# EGS002.net
KiCad netlist of a schematic drawn in Altium Designer
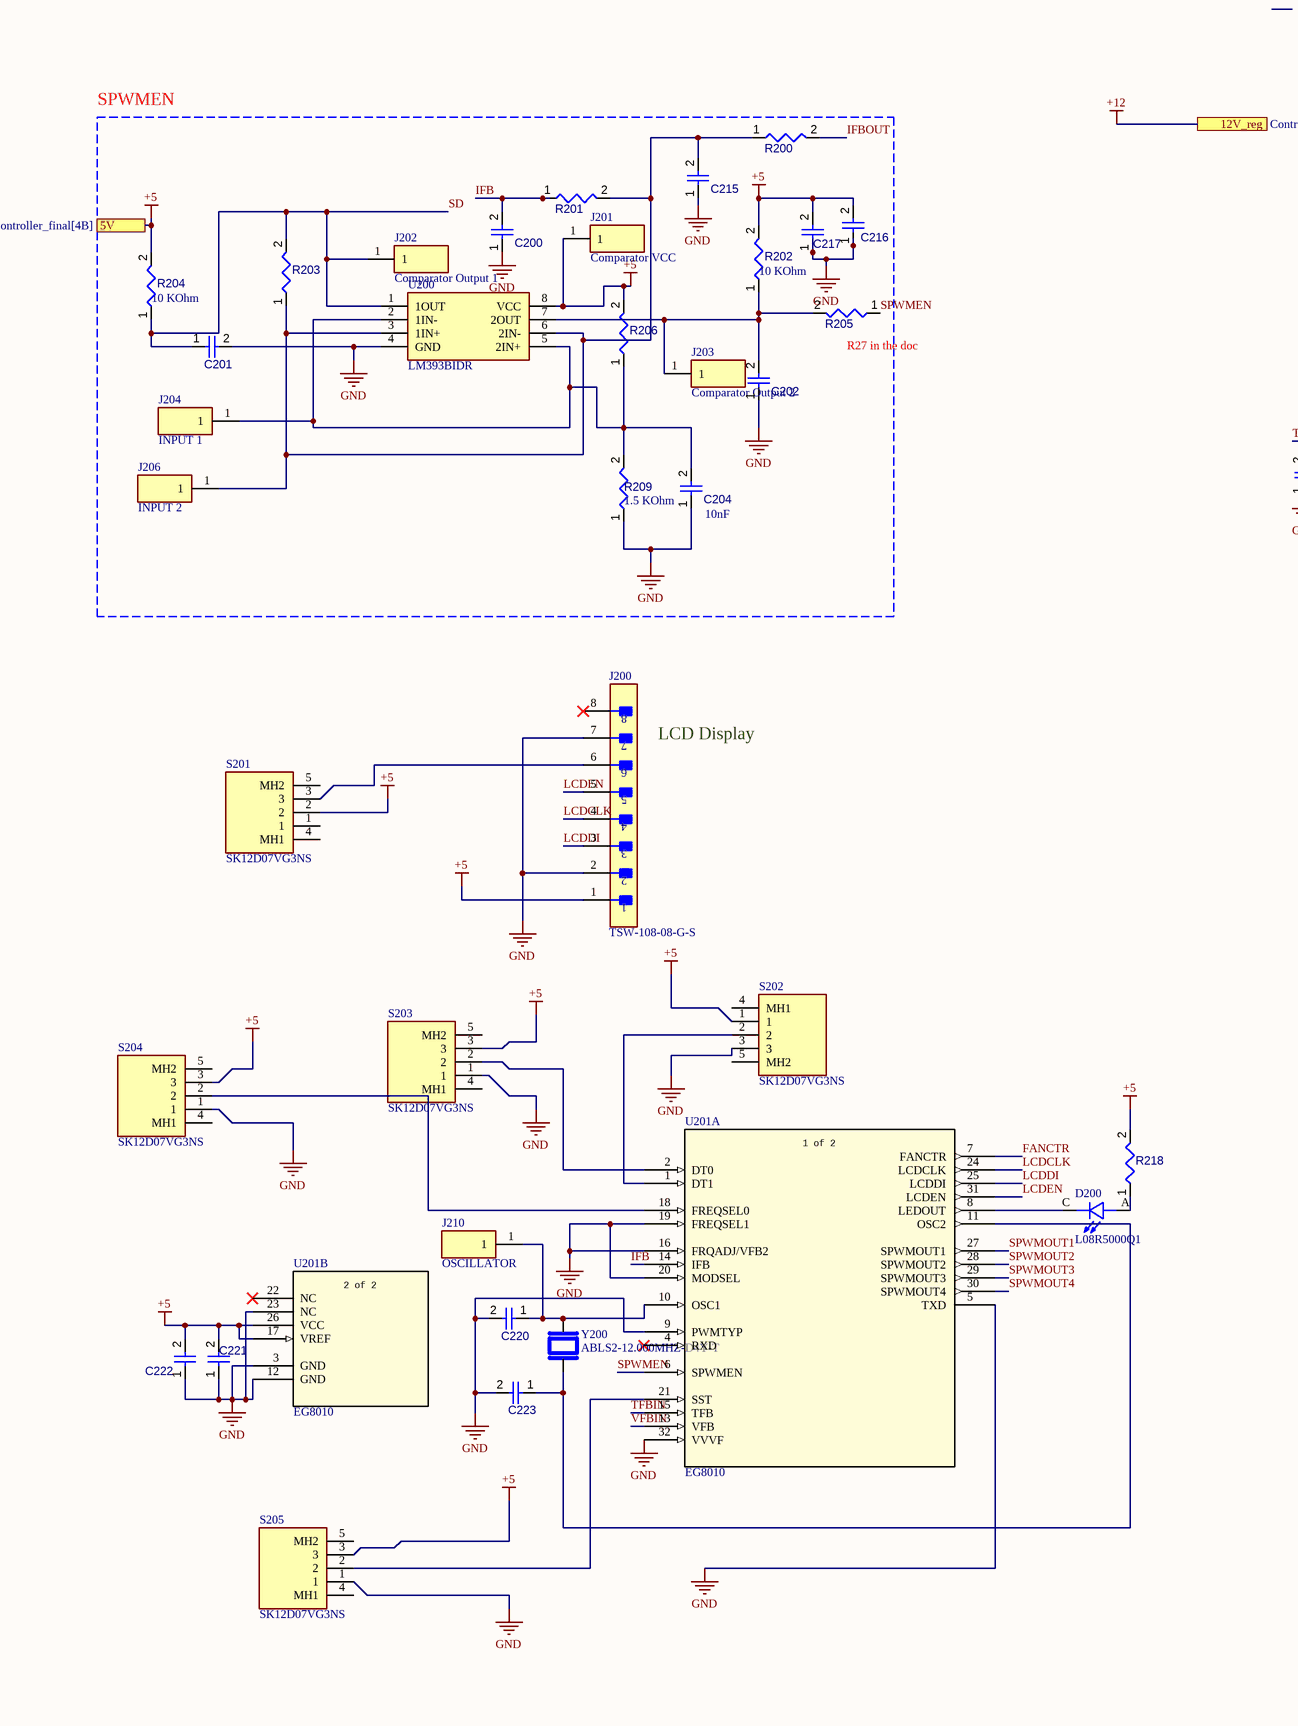
[diagram p0: EGS002.SchDoc, left]
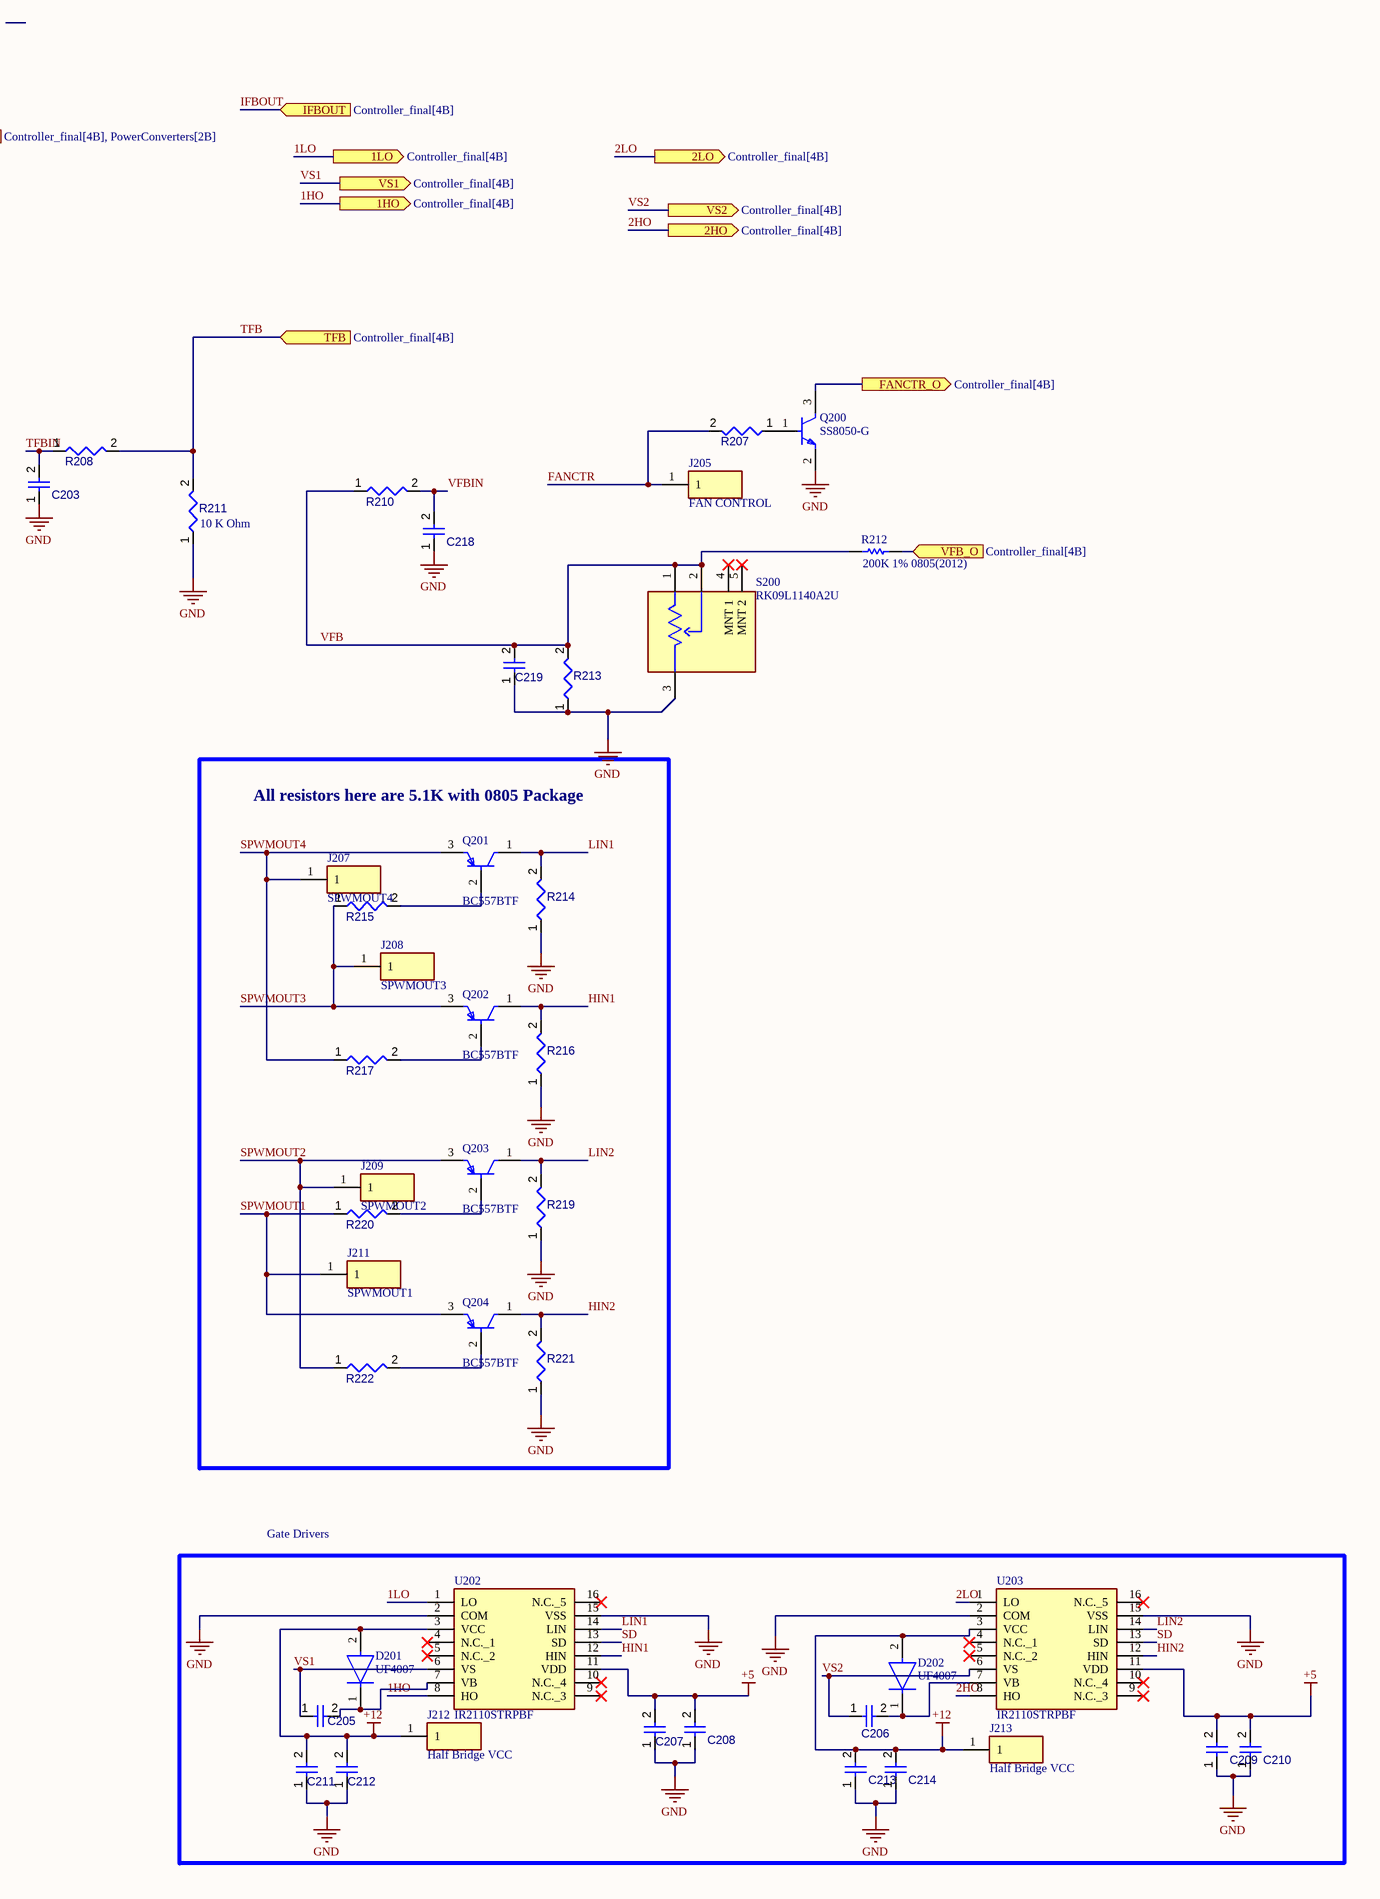
[diagram p1: EGS002.SchDoc, right]

(export (version "E")
  (design (tool "Eeschema 10.0.6"))
  (components
    (comp (ref "C200")
      (value "Capacitor 10nF +/-20% 50V 0402")
      (footprint "CAPC0402(1005)60_L")
      (description "Chip Capacitor, 10nF +/-20%, 50V, 0402, Thickness 0.6 mm")
      (fields (field (name "TOLERANCE") "5%"))
      (libsource (lib "Rahulb 23") (part "CAP-NP-2"))
    )
    (comp (ref "C201")
      (value "Capacitor 1nF +/-20% 50V 0402")
      (footprint "CAPC0402(1005)33_L")
      (description "Chip Capacitor, 1nF +/-20%, 50V, 0402, Thickness 0.33 mm")
      (fields (field (name "TOLERANCE") "10%"))
      (libsource (lib "Rahulb 23") (part "CAP-NP-2"))
    )
    (comp (ref "C202")
      (value "Capacitor 1nF +/-20% 50V 0402")
      (footprint "CAPC0402(1005)33_L")
      (description "Chip Capacitor, 1nF +/-20%, 50V, 0402, Thickness 0.33 mm")
      (fields (field (name "TOLERANCE") "10%"))
      (libsource (lib "Rahulb 23") (part "CAP-NP-2"))
    )
    (comp (ref "C203")
      (value "Capacitor 100 nF +/-10% 50 V 0805")
      (footprint "CAPC2013X95X50LL10T25")
      (description "Chip Capacitor, 100 nF, +/- 10%, 50 V, 0805 (2012 Metric)")
      (fields (field (name "TOLERANCE") "10%"))
      (libsource (lib "Rahulb 23") (part "CAP-NP-2"))
    )
    (comp (ref "C204")
      (value "Capacitor 10nF +/-20% 50V 0402")
      (footprint "CAPC0402(1005)60_L")
      (description "Chip Capacitor, 10nF +/-20%, 50V, 0402, Thickness 0.6 mm")
      (fields (field (name "TOLERANCE") "5%"))
      (libsource (lib "Rahulb 23") (part "CAP-NP-2"))
    )
    (comp (ref "C205")
      (value "Capacitor 10 uF +/- 10% 16 V 0805")
      (footprint "CAPC2013X135X45NL10T25")
      (description "Chip Capacitor, 10 uF, +/- 10%, 16 V, 0805 (2012 Metric)")
      (fields (field (name "TOLERANCE") "10%"))
      (libsource (lib "Rahulb 23") (part "CAP-NP-2"))
    )
    (comp (ref "C206")
      (value "Capacitor 10 uF +/- 10% 16 V 1206")
      (footprint "CAPC3216X180X50NL20T25")
      (description "Chip Capacitor, 10 uF, +/- 10%, 16 V, 1206 (3216 Metric)")
      (fields (field (name "TOLERANCE") "10%"))
      (libsource (lib "Rahulb 23") (part "CAP-NP-2"))
    )
    (comp (ref "C207")
      (value "Capacitor 100 nF +/-10% 50 V 0805")
      (footprint "CAPC2013X95X50LL10T25")
      (description "Chip Capacitor, 100 nF, +/- 10%, 50 V, 0805 (2012 Metric)")
      (fields (field (name "TOLERANCE") "10%"))
      (libsource (lib "Rahulb 23") (part "CAP-NP-2"))
    )
    (comp (ref "C208")
      (value "Capacitor 10 uF +/- 10% 16 V 1206")
      (footprint "CAPC3216X180X50NL20T25")
      (description "Chip Capacitor, 10 uF, +/- 10%, 16 V, 1206 (3216 Metric)")
      (fields (field (name "TOLERANCE") "10%"))
      (libsource (lib "Rahulb 23") (part "CAP-NP-2"))
    )
    (comp (ref "C209")
      (value "Capacitor 100 nF +/-10% 50 V 0805")
      (footprint "CAPC2013X95X50LL10T25")
      (description "Chip Capacitor, 100 nF, +/- 10%, 50 V, 0805 (2012 Metric)")
      (fields (field (name "TOLERANCE") "10%"))
      (libsource (lib "Rahulb 23") (part "CAP-NP-2"))
    )
    (comp (ref "C210")
      (value "Capacitor 10 uF +/- 10% 16 V 1206")
      (footprint "CAPC3216X180X50NL20T25")
      (description "Chip Capacitor, 10 uF, +/- 10%, 16 V, 1206 (3216 Metric)")
      (fields (field (name "TOLERANCE") "10%"))
      (libsource (lib "Rahulb 23") (part "CAP-NP-2"))
    )
    (comp (ref "C211")
      (value "Capacitor 100 nF +/-10% 50 V 0805")
      (footprint "CAPC2013X95X50LL10T25")
      (description "Chip Capacitor, 100 nF, +/- 10%, 50 V, 0805 (2012 Metric)")
      (fields (field (name "TOLERANCE") "10%"))
      (libsource (lib "Rahulb 23") (part "CAP-NP-2"))
    )
    (comp (ref "C212")
      (value "Capacitor 10 uF +/- 10% 16 V 1206")
      (footprint "CAPC3216X180X50NL20T25")
      (description "Chip Capacitor, 10 uF, +/- 10%, 16 V, 1206 (3216 Metric)")
      (fields (field (name "TOLERANCE") "10%"))
      (libsource (lib "Rahulb 23") (part "CAP-NP-2"))
    )
    (comp (ref "C213")
      (value "Capacitor 100 nF +/-10% 50 V 0805")
      (footprint "CAPC2013X95X50LL10T25")
      (description "Chip Capacitor, 100 nF, +/- 10%, 50 V, 0805 (2012 Metric)")
      (fields (field (name "TOLERANCE") "10%"))
      (libsource (lib "Rahulb 23") (part "CAP-NP-2"))
    )
    (comp (ref "C214")
      (value "Capacitor 10 uF +/- 10% 16 V 1206")
      (footprint "CAPC3216X180X50NL20T25")
      (description "Chip Capacitor, 10 uF, +/- 10%, 16 V, 1206 (3216 Metric)")
      (fields (field (name "TOLERANCE") "10%"))
      (libsource (lib "Rahulb 23") (part "CAP-NP-2"))
    )
    (comp (ref "C215")
      (value "Capacitor 1nF +/-20% 50V 0402")
      (footprint "CAPC0402(1005)33_L")
      (description "Chip Capacitor, 1nF +/-20%, 50V, 0402, Thickness 0.33 mm")
      (fields (field (name "TOLERANCE") "10%"))
      (libsource (lib "Rahulb 23") (part "CAP-NP-2"))
    )
    (comp (ref "C216")
      (value "Capacitor 10 uF +/- 10% 16 V 1206")
      (footprint "CAPC3216X180X50NL20T25")
      (description "Chip Capacitor, 10 uF, +/- 10%, 16 V, 1206 (3216 Metric)")
      (fields (field (name "TOLERANCE") "10%"))
      (libsource (lib "Rahulb 23") (part "CAP-NP-2"))
    )
    (comp (ref "C217")
      (value "Capacitor 100 nF +/-10% 50 V 0805")
      (footprint "CAPC2013X95X50LL10T25")
      (description "Chip Capacitor, 100 nF, +/- 10%, 50 V, 0805 (2012 Metric)")
      (fields (field (name "TOLERANCE") "10%"))
      (libsource (lib "Rahulb 23") (part "CAP-NP-2"))
    )
    (comp (ref "C218")
      (value "Capacitor 100 nF +/-10% 50 V 0805")
      (footprint "CAPC2013X95X50LL10T25")
      (description "Chip Capacitor, 100 nF, +/- 10%, 50 V, 0805 (2012 Metric)")
      (fields (field (name "TOLERANCE") "10%"))
      (libsource (lib "Rahulb 23") (part "CAP-NP-2"))
    )
    (comp (ref "C219")
      (value "Capacitor 100 nF +/-10% 50 V 0805")
      (footprint "CAPC2013X95X50LL10T25")
      (description "Chip Capacitor, 100 nF, +/- 10%, 50 V, 0805 (2012 Metric)")
      (fields (field (name "TOLERANCE") "10%"))
      (libsource (lib "Rahulb 23") (part "CAP-NP-2"))
    )
    (comp (ref "C220")
      (value "Capacitor 22pF +/-10% 50V 0402")
      (footprint "CAPC0402(1005)60_L")
      (description "Chip Capacitor, 22pF +/-10%, 50V, 0402, Thickness 0.6 mm")
      (fields (field (name "TOLERANCE") "10%"))
      (libsource (lib "Rahulb 23") (part "CAP-NP-2"))
    )
    (comp (ref "C221")
      (value "Capacitor 10 uF +/- 10% 16 V 1206")
      (footprint "CAPC3216X180X50NL20T25")
      (description "Chip Capacitor, 10 uF, +/- 10%, 16 V, 1206 (3216 Metric)")
      (fields (field (name "TOLERANCE") "10%"))
      (libsource (lib "Rahulb 23") (part "CAP-NP-2"))
    )
    (comp (ref "C222")
      (value "Capacitor 100 nF +/-10% 50 V 0805")
      (footprint "CAPC2013X95X50LL10T25")
      (description "Chip Capacitor, 100 nF, +/- 10%, 50 V, 0805 (2012 Metric)")
      (fields (field (name "TOLERANCE") "10%"))
      (libsource (lib "Rahulb 23") (part "CAP-NP-2"))
    )
    (comp (ref "C223")
      (value "Capacitor 22pF +/-10% 50V 0402")
      (footprint "CAPC0402(1005)60_L")
      (description "Chip Capacitor, 22pF +/-10%, 50V, 0402, Thickness 0.6 mm")
      (fields (field (name "TOLERANCE") "10%"))
      (libsource (lib "Rahulb 23") (part "CAP-NP-2"))
    )
    (comp (ref "D200")
      (value "L08R5000Q1")
      (footprint "LEDRD254W57D500H1070")
      (fields (field (name "MF") "LED Technology"))
      (libsource (lib "myComponents") (part "L08R5000Q1"))
    )
    (comp (ref "D201")
      (value "UF4007")
      (footprint "FP-017AH-MFG")
      (description "DIODE GEN PURP 1KV 1A DO41")
      (fields
        (field (name "MANUFACTURER") "ON Semiconductor")
        (field (name "OCTOPART") "https://octopart.com/uf4007-on+semiconductor-84331693")
      )
      (libsource (lib "Altium Content Vault") (part "d7152d700b627762746794eb795d46e"))
    )
    (comp (ref "D202")
      (value "UF4007")
      (footprint "FP-017AH-MFG")
      (description "DIODE GEN PURP 1KV 1A DO41")
      (fields
        (field (name "MANUFACTURER") "ON Semiconductor")
        (field (name "OCTOPART") "https://octopart.com/uf4007-on+semiconductor-84331693")
      )
      (libsource (lib "Altium Content Vault") (part "d7152d700b627762746794eb795d46e"))
    )
    (comp (ref "J200")
      (value "TSW-108-08-G-S")
      (footprint "FP-TSW-108-08-G-S-MFG")
      (description "CONN HEADER VERT 8POS 2.54MM")
      (fields
        (field (name "MANUFACTURER") "Samtec")
        (field (name "OCTOPART") "https://octopart.com/tsw-108-08-g-s-samtec-272653")
      )
      (libsource (lib "Altium Content Vault") (part "99ec2b232beb5d2356d4d77f6a047f0"))
    )
    (comp (ref "J201")
      (value "Comparator VCC")
      (footprint "SamacSys:5000")
      (description "C5277086")
      (fields (field (name "MANUFACTURER_PART_NUMBER") "5000") (field (name "MOUSER PART NUMBER") "534-5000"))
      (libsource (lib "myComponents") (part "5000"))
    )
    (comp (ref "J202")
      (value "Comparator Output 1")
      (footprint "SamacSys:5000")
      (description "C5277086")
      (fields (field (name "MANUFACTURER_PART_NUMBER") "5000") (field (name "MOUSER PART NUMBER") "534-5000"))
      (libsource (lib "myComponents") (part "5000"))
    )
    (comp (ref "J203")
      (value "Comparator Output 2")
      (footprint "SamacSys:5000")
      (description "C5277086")
      (fields (field (name "MANUFACTURER_PART_NUMBER") "5000") (field (name "MOUSER PART NUMBER") "534-5000"))
      (libsource (lib "myComponents") (part "5000"))
    )
    (comp (ref "J204")
      (value "INPUT 1")
      (footprint "SamacSys:5000")
      (description "C5277086")
      (fields (field (name "MANUFACTURER_PART_NUMBER") "5000") (field (name "MOUSER PART NUMBER") "534-5000"))
      (libsource (lib "") (part "5000_1"))
    )
    (comp (ref "J205")
      (value "FAN CONTROL")
      (footprint "SamacSys:5000")
      (description "C5277086")
      (fields (field (name "MANUFACTURER_PART_NUMBER") "5000") (field (name "MOUSER PART NUMBER") "534-5000"))
      (libsource (lib "myComponents") (part "5000"))
    )
    (comp (ref "J206")
      (value "INPUT 2")
      (footprint "SamacSys:5000")
      (description "C5277086")
      (fields (field (name "MANUFACTURER_PART_NUMBER") "5000") (field (name "MOUSER PART NUMBER") "534-5000"))
      (libsource (lib "") (part "5000_1"))
    )
    (comp (ref "J207")
      (value "SPWMOUT4")
      (footprint "SamacSys:5000")
      (description "C5277086")
      (fields (field (name "MANUFACTURER_PART_NUMBER") "5000") (field (name "MOUSER PART NUMBER") "534-5000"))
      (libsource (lib "myComponents") (part "5000"))
    )
    (comp (ref "J208")
      (value "SPWMOUT3")
      (footprint "SamacSys:5000")
      (description "Connector")
      (fields (field (name "MANUFACTURER_PART_NUMBER") "5000") (field (name "MOUSER PART NUMBER") "534-5000"))
      (libsource (lib "myComponents") (part "5000"))
    )
    (comp (ref "J209")
      (value "SPWMOUT2")
      (footprint "SamacSys:5000")
      (description "C5277086")
      (fields (field (name "MANUFACTURER_PART_NUMBER") "5000") (field (name "MOUSER PART NUMBER") "534-5000"))
      (libsource (lib "myComponents") (part "5000"))
    )
    (comp (ref "J210")
      (value "OSCILLATOR")
      (footprint "SamacSys:5000")
      (description "C5277086")
      (fields (field (name "MANUFACTURER_PART_NUMBER") "5000") (field (name "MOUSER PART NUMBER") "534-5000"))
      (libsource (lib "") (part "5000_1"))
    )
    (comp (ref "J211")
      (value "SPWMOUT1")
      (footprint "SamacSys:5000")
      (description "C5277086")
      (fields (field (name "MANUFACTURER_PART_NUMBER") "5000") (field (name "MOUSER PART NUMBER") "534-5000"))
      (libsource (lib "myComponents") (part "5000"))
    )
    (comp (ref "J212")
      (value "Half Bridge VCC")
      (footprint "SamacSys:5000")
      (description "C5277086")
      (fields (field (name "MANUFACTURER_PART_NUMBER") "5000") (field (name "MOUSER PART NUMBER") "534-5000"))
      (libsource (lib "myComponents") (part "5000"))
    )
    (comp (ref "J213")
      (value "Half Bridge VCC")
      (footprint "SamacSys:5000")
      (description "C5277086")
      (fields (field (name "MANUFACTURER_PART_NUMBER") "5000") (field (name "MOUSER PART NUMBER") "534-5000"))
      (libsource (lib "myComponents") (part "5000"))
    )
    (comp (ref "Q200")
      (value "SS8050-G")
      (footprint "FP-SS8050-G-MFG")
      (description "NPN TRANSISTOR 1.5A 40V SOT-23 R")
      (libsource (lib "Altium Content Vault") (part "2a1388f82443b098dcd57d24ac7632d"))
    )
    (comp (ref "Q201")
      (value "BC557BTF")
      (footprint "FP-135AR-MFG")
      (description "BC557BTF Small Signal Bipolar Transistor, 0.1A I(C), 45V V(BR)CEO, 1-Element, PNP, Silicon, TO-92")
      (libsource (lib "Altium Content Vault") (part "9e2844d3eb996af6824d2c99fe21afc"))
    )
    (comp (ref "Q202")
      (value "BC557BTF")
      (footprint "FP-135AR-MFG")
      (description "BC557BTF Small Signal Bipolar Transistor, 0.1A I(C), 45V V(BR)CEO, 1-Element, PNP, Silicon, TO-92")
      (libsource (lib "Altium Content Vault") (part "9e2844d3eb996af6824d2c99fe21afc"))
    )
    (comp (ref "Q203")
      (value "BC557BTF")
      (footprint "FP-135AR-MFG")
      (description "BC557BTF Small Signal Bipolar Transistor, 0.1A I(C), 45V V(BR)CEO, 1-Element, PNP, Silicon, TO-92")
      (libsource (lib "Altium Content Vault") (part "9e2844d3eb996af6824d2c99fe21afc"))
    )
    (comp (ref "Q204")
      (value "BC557BTF")
      (footprint "FP-135AR-MFG")
      (description "BC557BTF Small Signal Bipolar Transistor, 0.1A I(C), 45V V(BR)CEO, 1-Element, PNP, Silicon, TO-92")
      (libsource (lib "Altium Content Vault") (part "9e2844d3eb996af6824d2c99fe21afc"))
    )
    (comp (ref "R200")
      (value "Resistor 1K +/-5% 0805 125 mW")
      (footprint "RESC0805(2012)_L")
      (description "Chip Resistor, 1 kOhms, +/-5%, 125 mW, -55 to 155 degC, 0805")
      (fields (field (name "TOLERANCE") "5%") (field (name "POWER") "125mW"))
      (libsource (lib "Rahulb 23") (part "RES-2"))
    )
    (comp (ref "R201")
      (value "Resistor 100k +/-1% 0805 125 mW")
      (footprint "RESC2013X70X40ML20T20")
      (description "Chip Resistor, 100 KOhm, +/- 1%, 0.125 W, -55 to 155 degC, 0805 (2012 Metric)")
      (fields (field (name "TOLERANCE") "1%") (field (name "POWER") "125mW"))
      (libsource (lib "Rahulb 23") (part "RES-2"))
    )
    (comp (ref "R202")
      (value "Resistor 10k +/-1% 0805 125 mW")
      (footprint "RESC2013X50X35ML15T15")
      (description "Chip Resistor, 10 KOhm, +/- 1%, 125 mW, -55 to 155 degC, 0805 (2012 Metric)")
      (fields (field (name "TOLERANCE") "1%") (field (name "POWER") "125mW"))
      (libsource (lib "Rahulb 23") (part "RES-2"))
    )
    (comp (ref "R203")
      (value "Resistor 100k +/-1% 0805 125 mW")
      (footprint "RESC2013X70X40ML20T20")
      (description "Chip Resistor, 100 KOhm, +/- 1%, 0.125 W, -55 to 155 degC, 0805 (2012 Metric)")
      (fields (field (name "TOLERANCE") "1%") (field (name "POWER") "125mW"))
      (libsource (lib "Rahulb 23") (part "RES-2"))
    )
    (comp (ref "R204")
      (value "Resistor 10k +/-1% 0805 125 mW")
      (footprint "RESC2013X50X35ML15T15")
      (description "Chip Resistor, 10 KOhm, +/- 1%, 125 mW, -55 to 155 degC, 0805 (2012 Metric)")
      (fields (field (name "TOLERANCE") "1%") (field (name "POWER") "125mW"))
      (libsource (lib "Rahulb 23") (part "RES-2"))
    )
    (comp (ref "R205")
      (value "Resistor 1.5k +/-1% 0805 125 mW")
      (footprint "RESC2013X50X35ML15T15")
      (description "Chip Resistor, 1.5 KOhm, +/- 1%, 125 mW, -55 to 155 degC, 0805 (2012 Metric)")
      (fields (field (name "TOLERANCE") "1%") (field (name "POWER") "125mW"))
      (libsource (lib "Rahulb 23") (part "RES-2"))
    )
    (comp (ref "R206")
      (value "Resistor 10k +/-1% 0805 125 mW")
      (footprint "RESC2013X50X35ML15T15")
      (description "Chip Resistor, 10 KOhm, +/- 1%, 125 mW, -55 to 155 degC, 0805 (2012 Metric)")
      (fields (field (name "TOLERANCE") "1%") (field (name "POWER") "125mW"))
      (libsource (lib "Rahulb 23") (part "RES-2"))
    )
    (comp (ref "R207")
      (value "Resistor 1.5k +/-1% 0805 125 mW")
      (footprint "RESC2013X50X35ML15T15")
      (description "Chip Resistor, 1.5 KOhm, +/- 1%, 125 mW, -55 to 155 degC, 0805 (2012 Metric)")
      (fields (field (name "TOLERANCE") "1%") (field (name "POWER") "125mW"))
      (libsource (lib "Rahulb 23") (part "RES-2"))
    )
    (comp (ref "R208")
      (value "Resistor 100R +/-1 % 0402 63 mW")
      (footprint "RESC0402(1005)_L")
      (description "Chip Resistor, 100 Ohms, +/-1 %, 63 mW, -55 to 155 degC, 0402")
      (fields (field (name "TOLERANCE") "1%") (field (name "POWER") "63mW"))
      (libsource (lib "Rahulb 23") (part "RES-2"))
    )
    (comp (ref "R209")
      (value "Resistor 1.5k +/-1% 0805 125 mW")
      (footprint "RESC2013X50X35ML15T15")
      (description "Chip Resistor, 1.5 KOhm, +/- 1%, 125 mW, -55 to 155 degC, 0805 (2012 Metric)")
      (fields (field (name "TOLERANCE") "1%") (field (name "POWER") "125mW"))
      (libsource (lib "Rahulb 23") (part "RES-2"))
    )
    (comp (ref "R210")
      (value "Resistor 100R +/-1 % 0402 63 mW")
      (footprint "RESC0402(1005)_L")
      (description "Chip Resistor, 100 Ohms, +/-1 %, 63 mW, -55 to 155 degC, 0402")
      (fields (field (name "TOLERANCE") "1%") (field (name "POWER") "63mW"))
      (libsource (lib "Rahulb 23") (part "RES-2"))
    )
    (comp (ref "R211")
      (value "Resistor 10k +/-1% 0805 125 mW")
      (footprint "RESC2013X50X35ML15T15")
      (description "Chip Resistor, 10 KOhm, +/- 1%, 125 mW, -55 to 155 degC, 0805 (2012 Metric)")
      (fields (field (name "TOLERANCE") "1%") (field (name "POWER") "125mW"))
      (libsource (lib "Rahulb 23") (part "RES-2"))
    )
    (comp (ref "R212")
      (value "200K 1% 0805(2012)")
      (footprint "RESC0805(2012)_N")
      (description "200K 0.125W 1% 0805 (2012 Metric)  SMD")
      (fields (field (name "POWER") "0.125 W") (field (name "TOLERANCE") "1 %"))
      (libsource (lib "Altium Content Vault") (part "RES"))
    )
    (comp (ref "R213")
      (value "Resistor 10k +/-1% 0805 125 mW")
      (footprint "RESC2013X50X35ML15T15")
      (description "Chip Resistor, 10 KOhm, +/- 1%, 125 mW, -55 to 155 degC, 0805 (2012 Metric)")
      (fields (field (name "TOLERANCE") "1%") (field (name "POWER") "125mW"))
      (libsource (lib "Rahulb 23") (part "RES-2"))
    )
    (comp (ref "R214")
      (value "Resistor 5.1k +/-1% 0805 125 mW")
      (footprint "RESC2013X50X35ML15T15")
      (description "Chip Resistor, 5.1 KOhm, +/- 1%, 125 mW, -55 to 155 degC, 0805 (2012 Metric)")
      (fields (field (name "TOLERANCE") "1%") (field (name "POWER") "125mW"))
      (libsource (lib "Rahulb 23") (part "RES-2"))
    )
    (comp (ref "R215")
      (value "Resistor 5.1k +/-1% 0805 125 mW")
      (footprint "RESC2013X50X35ML15T15")
      (description "Chip Resistor, 5.1 KOhm, +/- 1%, 125 mW, -55 to 155 degC, 0805 (2012 Metric)")
      (fields (field (name "TOLERANCE") "1%") (field (name "POWER") "125mW"))
      (libsource (lib "Rahulb 23") (part "RES-2"))
    )
    (comp (ref "R216")
      (value "Resistor 5.1k +/-1% 0805 125 mW")
      (footprint "RESC2013X50X35ML15T15")
      (description "Chip Resistor, 5.1 KOhm, +/- 1%, 125 mW, -55 to 155 degC, 0805 (2012 Metric)")
      (fields (field (name "TOLERANCE") "1%") (field (name "POWER") "125mW"))
      (libsource (lib "Rahulb 23") (part "RES-2"))
    )
    (comp (ref "R217")
      (value "Resistor 5.1k +/-1% 0805 125 mW")
      (footprint "RESC2013X50X35ML15T15")
      (description "Chip Resistor, 5.1 KOhm, +/- 1%, 125 mW, -55 to 155 degC, 0805 (2012 Metric)")
      (fields (field (name "TOLERANCE") "1%") (field (name "POWER") "125mW"))
      (libsource (lib "Rahulb 23") (part "RES-2"))
    )
    (comp (ref "R218")
      (value "Resistor 1K +/-5% 0805 125 mW")
      (footprint "RESC0805(2012)_L")
      (description "Chip Resistor, 1 kOhms, +/-5%, 125 mW, -55 to 155 degC, 0805")
      (fields (field (name "TOLERANCE") "5%") (field (name "POWER") "125mW"))
      (libsource (lib "Rahulb 23") (part "RES-2"))
    )
    (comp (ref "R219")
      (value "Resistor 5.1k +/-1% 0805 125 mW")
      (footprint "RESC2013X50X35ML15T15")
      (description "Chip Resistor, 5.1 KOhm, +/- 1%, 125 mW, -55 to 155 degC, 0805 (2012 Metric)")
      (fields (field (name "TOLERANCE") "1%") (field (name "POWER") "125mW"))
      (libsource (lib "Rahulb 23") (part "RES-2"))
    )
    (comp (ref "R220")
      (value "Resistor 5.1k +/-1% 0805 125 mW")
      (footprint "RESC2013X50X35ML15T15")
      (description "Chip Resistor, 5.1 KOhm, +/- 1%, 125 mW, -55 to 155 degC, 0805 (2012 Metric)")
      (fields (field (name "TOLERANCE") "1%") (field (name "POWER") "125mW"))
      (libsource (lib "Rahulb 23") (part "RES-2"))
    )
    (comp (ref "R221")
      (value "Resistor 5.1k +/-1% 0805 125 mW")
      (footprint "RESC2013X50X35ML15T15")
      (description "Chip Resistor, 5.1 KOhm, +/- 1%, 125 mW, -55 to 155 degC, 0805 (2012 Metric)")
      (fields (field (name "TOLERANCE") "1%") (field (name "POWER") "125mW"))
      (libsource (lib "Rahulb 23") (part "RES-2"))
    )
    (comp (ref "R222")
      (value "Resistor 5.1k +/-1% 0805 125 mW")
      (footprint "RESC2013X50X35ML15T15")
      (description "Chip Resistor, 5.1 KOhm, +/- 1%, 125 mW, -55 to 155 degC, 0805 (2012 Metric)")
      (fields (field (name "TOLERANCE") "1%") (field (name "POWER") "125mW"))
      (libsource (lib "Rahulb 23") (part "RES-2"))
    )
    (comp (ref "S200")
      (value "RK09L1140A2U")
      (footprint "FP-RK09L1140A2U-MFG")
      (description "9mm Size Metal Shaft Snap-in Type RK09L Series")
      (fields
        (field (name "TOLERANCE") "20%")
        (field (name "OCTOPART") "https://octopart.com/rk09l1140a2u-alps-7850070")
      )
      (libsource (lib "Altium Content Vault") (part "0c568a6e0ac31b8b52ae5f6704acd43"))
    )
    (comp (ref "S201")
      (value "SK12D07VG3NS")
      (footprint "SK12D07VG3NS")
      (description "SK12D07VG3")
      (fields (field (name "MOUSER PART NUMBER") "611-SK12D07VG3NS"))
      (libsource (lib "myComponents") (part "SK12D07VG3NS"))
    )
    (comp (ref "S202")
      (value "SK12D07VG3NS")
      (footprint "SK12D07VG3NS")
      (description "SK12D07VG3")
      (fields (field (name "MOUSER PART NUMBER") "611-SK12D07VG3NS"))
      (libsource (lib "") (part "SK12D07VG3NS_1"))
    )
    (comp (ref "S203")
      (value "SK12D07VG3NS")
      (footprint "SK12D07VG3NS")
      (description "SK12D07VG3")
      (fields (field (name "MOUSER PART NUMBER") "611-SK12D07VG3NS"))
      (libsource (lib "myComponents") (part "SK12D07VG3NS"))
    )
    (comp (ref "S204")
      (value "SK12D07VG3NS")
      (footprint "SK12D07VG3NS")
      (description "SK12D07VG3")
      (fields (field (name "MOUSER PART NUMBER") "611-SK12D07VG3NS"))
      (libsource (lib "myComponents") (part "SK12D07VG3NS"))
    )
    (comp (ref "S205")
      (value "SK12D07VG3NS")
      (footprint "SK12D07VG3NS")
      (description "SK12D07VG3")
      (fields (field (name "MOUSER PART NUMBER") "611-SK12D07VG3NS"))
      (libsource (lib "myComponents") (part "SK12D07VG3NS"))
    )
    (comp (ref "U200")
      (value "LM393BIDR")
      (footprint "SOIC127P600X175-8N")
      (description "Analog Comparators Dual standard comparator 8-SOIC -40 to 85")
      (fields (field (name "MOUSER PART NUMBER") "595-LM393BIDR"))
      (libsource (lib "myComponents") (part "LM393BIDR"))
    )
    (comp (ref "U201")
      (value "EG8010")
      (footprint "EG8010")
      (description "Description")
      (fields (field (name "COPYRIGHT") "Copyright (C) 2026 Ultra Librarian. All rights reserved."))
      (libsource (lib "myComponents") (part "EG8010"))
    )
    (comp (ref "U202")
      (value "IR2110STRPBF")
      (footprint "IR2110S")
      (libsource (lib "myComponents") (part "IR2110S"))
    )
    (comp (ref "U203")
      (value "IR2110STRPBF")
      (footprint "IR2110S")
      (libsource (lib "myComponents") (part "IR2110S"))
    )
    (comp (ref "Y200")
      (value "ABLS2-12.000MHZ-D4Y-T")
      (footprint "XTAL_ABLS2-12.000MHZ-D4Y-T")
      (description "HC/49US (AT49) LOW PROFILE SURFACE MOUNT MICROPROCESSOR CRYSTAL")
      (fields (field (name "MF") "Abracon"))
      (libsource (lib "myComponents") (part "ABLS2-12.000MHZ-D4Y-T"))
    )
  )
  (nets
    (net (code "1") (name "+5") (class "Default")
      (node (ref "C207") (pin "2") (pinfunction "2_2") (pintype "passive"))
      (node (ref "C208") (pin "2") (pinfunction "2_2") (pintype "passive"))
      (node (ref "C209") (pin "2") (pinfunction "2_2") (pintype "passive"))
      (node (ref "C210") (pin "2") (pinfunction "2_2") (pintype "passive"))
      (node (ref "C216") (pin "2") (pinfunction "2_2") (pintype "passive"))
      (node (ref "C217") (pin "2") (pinfunction "2_2") (pintype "passive"))
      (node (ref "C221") (pin "2") (pinfunction "2_2") (pintype "passive"))
      (node (ref "C222") (pin "2") (pinfunction "2_2") (pintype "passive"))
      (node (ref "J200") (pin "1") (pinfunction "1_1") (pintype "passive"))
      (node (ref "J201") (pin "1") (pinfunction "1_1") (pintype "passive"))
      (node (ref "R202") (pin "2") (pinfunction "2_2") (pintype "passive"))
      (node (ref "R204") (pin "2") (pinfunction "2_2") (pintype "passive"))
      (node (ref "R206") (pin "2") (pinfunction "2_2") (pintype "passive"))
      (node (ref "R218") (pin "2") (pinfunction "2_2") (pintype "passive"))
      (node (ref "S201") (pin "2") (pinfunction "2_2") (pintype "passive"))
      (node (ref "S202") (pin "1") (pinfunction "1_1") (pintype "passive"))
      (node (ref "S203") (pin "3") (pinfunction "3_3") (pintype "passive"))
      (node (ref "S204") (pin "3") (pinfunction "3_3") (pintype "passive"))
      (node (ref "S205") (pin "3") (pinfunction "3_3") (pintype "passive"))
      (node (ref "U200") (pin "8") (pinfunction "VCC_8") (pintype "passive"))
      (node (ref "U201") (pin "17") (pinfunction "VREF_17") (pintype "input"))
      (node (ref "U201") (pin "26") (pinfunction "VCC_26") (pintype "power_in"))
      (node (ref "U202") (pin "11") (pinfunction "VDD_11") (pintype "passive"))
      (node (ref "U203") (pin "11") (pinfunction "VDD_11") (pintype "passive"))
    )
    (net (code "2") (name "+12") (class "Default")
      (node (ref "C211") (pin "2") (pinfunction "2_2") (pintype "passive"))
      (node (ref "C212") (pin "2") (pinfunction "2_2") (pintype "passive"))
      (node (ref "C213") (pin "2") (pinfunction "2_2") (pintype "passive"))
      (node (ref "C214") (pin "2") (pinfunction "2_2") (pintype "passive"))
      (node (ref "D201") (pin "2") (pinfunction "A_2") (pintype "passive"))
      (node (ref "D202") (pin "2") (pinfunction "A_2") (pintype "passive"))
      (node (ref "J212") (pin "1") (pinfunction "1_1") (pintype "passive"))
      (node (ref "J213") (pin "1") (pinfunction "1_1") (pintype "passive"))
      (node (ref "U202") (pin "3") (pinfunction "VCC_3") (pintype "passive"))
      (node (ref "U203") (pin "3") (pinfunction "VCC_3") (pintype "passive"))
    )
    (net (code "3") (name "/1HO") (class "Default")
      (node (ref "U202") (pin "8") (pinfunction "HO_8") (pintype "passive"))
    )
    (net (code "4") (name "/1LO") (class "Default")
      (node (ref "U202") (pin "1") (pinfunction "LO_1") (pintype "passive"))
    )
    (net (code "5") (name "/2HO") (class "Default")
      (node (ref "U203") (pin "8") (pinfunction "HO_8") (pintype "passive"))
    )
    (net (code "6") (name "/2LO") (class "Default")
      (node (ref "U203") (pin "1") (pinfunction "LO_1") (pintype "passive"))
    )
    (net (code "7") (name "/FANCTR") (class "Default")
      (node (ref "J205") (pin "1") (pinfunction "1_1") (pintype "passive"))
      (node (ref "R207") (pin "2") (pinfunction "2_2") (pintype "passive"))
      (node (ref "U201") (pin "7") (pinfunction "FANCTR_7") (pintype "output"))
    )
    (net (code "8") (name "/FANCTR_O") (class "Default")
      (node (ref "Q200") (pin "3") (pinfunction "C_3") (pintype "passive"))
    )
    (net (code "9") (name "/HIN1") (class "Default")
      (node (ref "Q202") (pin "1") (pinfunction "C_1") (pintype "passive"))
      (node (ref "R216") (pin "2") (pinfunction "2_2") (pintype "passive"))
      (node (ref "U202") (pin "12") (pinfunction "HIN_12") (pintype "passive"))
    )
    (net (code "10") (name "/HIN2") (class "Default")
      (node (ref "Q204") (pin "1") (pinfunction "C_1") (pintype "passive"))
      (node (ref "R221") (pin "2") (pinfunction "2_2") (pintype "passive"))
      (node (ref "U203") (pin "12") (pinfunction "HIN_12") (pintype "passive"))
    )
    (net (code "11") (name "/IFB") (class "Default")
      (node (ref "C200") (pin "2") (pinfunction "2_2") (pintype "passive"))
      (node (ref "R201") (pin "1") (pinfunction "1_1") (pintype "passive"))
      (node (ref "U201") (pin "14") (pinfunction "IFB_14") (pintype "input"))
    )
    (net (code "12") (name "/IFBOUT") (class "Default")
      (node (ref "R200") (pin "2") (pinfunction "2_2") (pintype "passive"))
    )
    (net (code "13") (name "/LCDCLK") (class "Default")
      (node (ref "J200") (pin "4") (pinfunction "4_4") (pintype "passive"))
      (node (ref "U201") (pin "24") (pinfunction "LCDCLK_24") (pintype "output"))
    )
    (net (code "14") (name "/LCDDI") (class "Default")
      (node (ref "J200") (pin "3") (pinfunction "3_3") (pintype "passive"))
      (node (ref "U201") (pin "25") (pinfunction "LCDDI_25") (pintype "output"))
    )
    (net (code "15") (name "/LCDEN") (class "Default")
      (node (ref "J200") (pin "5") (pinfunction "5_5") (pintype "passive"))
      (node (ref "U201") (pin "31") (pinfunction "LCDEN_31") (pintype "output"))
    )
    (net (code "16") (name "/LIN1") (class "Default")
      (node (ref "Q201") (pin "1") (pinfunction "C_1") (pintype "passive"))
      (node (ref "R214") (pin "2") (pinfunction "2_2") (pintype "passive"))
      (node (ref "U202") (pin "14") (pinfunction "LIN_14") (pintype "passive"))
    )
    (net (code "17") (name "/LIN2") (class "Default")
      (node (ref "Q203") (pin "1") (pinfunction "C_1") (pintype "passive"))
      (node (ref "R219") (pin "2") (pinfunction "2_2") (pintype "passive"))
      (node (ref "U203") (pin "14") (pinfunction "LIN_14") (pintype "passive"))
    )
    (net (code "18") (name "/SD") (class "Default")
      (node (ref "C201") (pin "1") (pinfunction "1_1") (pintype "passive"))
      (node (ref "J202") (pin "1") (pinfunction "1_1") (pintype "passive"))
      (node (ref "R203") (pin "2") (pinfunction "2_2") (pintype "passive"))
      (node (ref "R204") (pin "1") (pinfunction "1_1") (pintype "passive"))
      (node (ref "U200") (pin "1") (pinfunction "1OUT_1") (pintype "passive"))
      (node (ref "U202") (pin "13") (pinfunction "SD_13") (pintype "passive"))
      (node (ref "U203") (pin "13") (pinfunction "SD_13") (pintype "passive"))
    )
    (net (code "19") (name "/SPWMEN") (class "Default")
      (node (ref "R205") (pin "1") (pinfunction "1_1") (pintype "passive"))
      (node (ref "U201") (pin "6") (pinfunction "SPWMEN_6") (pintype "input"))
    )
    (net (code "20") (name "/SPWMOUT1") (class "Default")
      (node (ref "J211") (pin "1") (pinfunction "1_1") (pintype "passive"))
      (node (ref "Q204") (pin "3") (pinfunction "E_3") (pintype "passive"))
      (node (ref "R220") (pin "1") (pinfunction "1_1") (pintype "passive"))
      (node (ref "U201") (pin "27") (pinfunction "SPWMOUT1_27") (pintype "output"))
    )
    (net (code "21") (name "/SPWMOUT2") (class "Default")
      (node (ref "J209") (pin "1") (pinfunction "1_1") (pintype "passive"))
      (node (ref "Q203") (pin "3") (pinfunction "E_3") (pintype "passive"))
      (node (ref "R222") (pin "1") (pinfunction "1_1") (pintype "passive"))
      (node (ref "U201") (pin "28") (pinfunction "SPWMOUT2_28") (pintype "output"))
    )
    (net (code "22") (name "/SPWMOUT3") (class "Default")
      (node (ref "J208") (pin "1") (pinfunction "1_1") (pintype "passive"))
      (node (ref "Q202") (pin "3") (pinfunction "E_3") (pintype "passive"))
      (node (ref "R215") (pin "1") (pinfunction "1_1") (pintype "passive"))
      (node (ref "U201") (pin "29") (pinfunction "SPWMOUT3_29") (pintype "output"))
    )
    (net (code "23") (name "/SPWMOUT4") (class "Default")
      (node (ref "J207") (pin "1") (pinfunction "1_1") (pintype "passive"))
      (node (ref "Q201") (pin "3") (pinfunction "E_3") (pintype "passive"))
      (node (ref "R217") (pin "1") (pinfunction "1_1") (pintype "passive"))
      (node (ref "U201") (pin "30") (pinfunction "SPWMOUT4_30") (pintype "output"))
    )
    (net (code "24") (name "/TFB") (class "Default")
      (node (ref "R208") (pin "2") (pinfunction "2_2") (pintype "passive"))
      (node (ref "R211") (pin "2") (pinfunction "2_2") (pintype "passive"))
    )
    (net (code "25") (name "/TFBIN") (class "Default")
      (node (ref "C203") (pin "2") (pinfunction "2_2") (pintype "passive"))
      (node (ref "R208") (pin "1") (pinfunction "1_1") (pintype "passive"))
      (node (ref "U201") (pin "15") (pinfunction "TFB_15") (pintype "input"))
    )
    (net (code "26") (name "/VFB") (class "Default")
      (node (ref "C219") (pin "2") (pinfunction "2_2") (pintype "passive"))
      (node (ref "R210") (pin "1") (pinfunction "1_1") (pintype "passive"))
      (node (ref "R212") (pin "1") (pinfunction "1_1") (pintype "passive"))
      (node (ref "R213") (pin "2") (pinfunction "2_2") (pintype "passive"))
      (node (ref "S200") (pin "1") (pinfunction "1_1") (pintype "passive"))
      (node (ref "S200") (pin "2") (pinfunction "2_2") (pintype "passive"))
    )
    (net (code "27") (name "/VFBIN") (class "Default")
      (node (ref "C218") (pin "2") (pinfunction "2_2") (pintype "passive"))
      (node (ref "R210") (pin "2") (pinfunction "2_2") (pintype "passive"))
      (node (ref "U201") (pin "13") (pinfunction "VFB_13") (pintype "input"))
    )
    (net (code "28") (name "/VFB_O") (class "Default")
      (node (ref "R212") (pin "2") (pinfunction "2_2") (pintype "passive"))
    )
    (net (code "29") (name "/VS1") (class "Default")
      (node (ref "C205") (pin "1") (pinfunction "1_1") (pintype "passive"))
      (node (ref "U202") (pin "6") (pinfunction "VS_6") (pintype "passive"))
    )
    (net (code "30") (name "/VS2") (class "Default")
      (node (ref "C206") (pin "1") (pinfunction "1_1") (pintype "passive"))
      (node (ref "U203") (pin "6") (pinfunction "VS_6") (pintype "passive"))
    )
    (net (code "31") (name "GND") (class "Default")
      (node (ref "C200") (pin "1") (pinfunction "1_1") (pintype "passive"))
      (node (ref "C201") (pin "2") (pinfunction "2_2") (pintype "passive"))
      (node (ref "C202") (pin "1") (pinfunction "1_1") (pintype "passive"))
      (node (ref "C203") (pin "1") (pinfunction "1_1") (pintype "passive"))
      (node (ref "C204") (pin "1") (pinfunction "1_1") (pintype "passive"))
      (node (ref "C207") (pin "1") (pinfunction "1_1") (pintype "passive"))
      (node (ref "C208") (pin "1") (pinfunction "1_1") (pintype "passive"))
      (node (ref "C209") (pin "1") (pinfunction "1_1") (pintype "passive"))
      (node (ref "C210") (pin "1") (pinfunction "1_1") (pintype "passive"))
      (node (ref "C211") (pin "1") (pinfunction "1_1") (pintype "passive"))
      (node (ref "C212") (pin "1") (pinfunction "1_1") (pintype "passive"))
      (node (ref "C213") (pin "1") (pinfunction "1_1") (pintype "passive"))
      (node (ref "C214") (pin "1") (pinfunction "1_1") (pintype "passive"))
      (node (ref "C215") (pin "1") (pinfunction "1_1") (pintype "passive"))
      (node (ref "C216") (pin "1") (pinfunction "1_1") (pintype "passive"))
      (node (ref "C217") (pin "1") (pinfunction "1_1") (pintype "passive"))
      (node (ref "C218") (pin "1") (pinfunction "1_1") (pintype "passive"))
      (node (ref "C219") (pin "1") (pinfunction "1_1") (pintype "passive"))
      (node (ref "C220") (pin "2") (pinfunction "2_2") (pintype "passive"))
      (node (ref "C221") (pin "1") (pinfunction "1_1") (pintype "passive"))
      (node (ref "C222") (pin "1") (pinfunction "1_1") (pintype "passive"))
      (node (ref "C223") (pin "2") (pinfunction "2_2") (pintype "passive"))
      (node (ref "J200") (pin "2") (pinfunction "2_2") (pintype "passive"))
      (node (ref "J200") (pin "7") (pinfunction "7_7") (pintype "passive"))
      (node (ref "Q200") (pin "2") (pinfunction "E_2") (pintype "passive"))
      (node (ref "R209") (pin "1") (pinfunction "1_1") (pintype "passive"))
      (node (ref "R211") (pin "1") (pinfunction "1_1") (pintype "passive"))
      (node (ref "R213") (pin "1") (pinfunction "1_1") (pintype "passive"))
      (node (ref "R214") (pin "1") (pinfunction "1_1") (pintype "passive"))
      (node (ref "R216") (pin "1") (pinfunction "1_1") (pintype "passive"))
      (node (ref "R219") (pin "1") (pinfunction "1_1") (pintype "passive"))
      (node (ref "R221") (pin "1") (pinfunction "1_1") (pintype "passive"))
      (node (ref "S200") (pin "3") (pinfunction "3_3") (pintype "passive"))
      (node (ref "S202") (pin "3") (pinfunction "3_3") (pintype "passive"))
      (node (ref "S203") (pin "1") (pinfunction "1_1") (pintype "passive"))
      (node (ref "S204") (pin "1") (pinfunction "1_1") (pintype "passive"))
      (node (ref "S205") (pin "1") (pinfunction "1_1") (pintype "passive"))
      (node (ref "U200") (pin "4") (pinfunction "GND_4") (pintype "passive"))
      (node (ref "U201") (pin "12") (pinfunction "GND_12") (pintype "passive"))
      (node (ref "U201") (pin "16") (pinfunction "FRQADJ/VFB2_16") (pintype "input"))
      (node (ref "U201") (pin "19") (pinfunction "FREQSEL1_19") (pintype "input"))
      (node (ref "U201") (pin "20") (pinfunction "MODSEL_20") (pintype "input"))
      (node (ref "U201") (pin "23") (pinfunction "NC_23") (pintype "passive"))
      (node (ref "U201") (pin "3") (pinfunction "GND_3") (pintype "passive"))
      (node (ref "U201") (pin "32") (pinfunction "VVVF_32") (pintype "input"))
      (node (ref "U201") (pin "5") (pinfunction "TXD_5") (pintype "passive"))
      (node (ref "U201") (pin "9") (pinfunction "PWMTYP_9") (pintype "input"))
      (node (ref "U202") (pin "15") (pinfunction "VSS_15") (pintype "passive"))
      (node (ref "U202") (pin "2") (pinfunction "COM_2") (pintype "passive"))
      (node (ref "U203") (pin "15") (pinfunction "VSS_15") (pintype "passive"))
      (node (ref "U203") (pin "2") (pinfunction "COM_2") (pintype "passive"))
    )
    (net (code "32") (name "Net-(D200-PadA)") (class "Default")
      (node (ref "D200") (pin "A") (pinfunction "A_A") (pintype "passive"))
      (node (ref "R218") (pin "1") (pinfunction "1_1") (pintype "passive"))
    )
    (net (code "33") (name "Net-(D201-C)") (class "Default")
      (node (ref "C205") (pin "2") (pinfunction "2_2") (pintype "passive"))
      (node (ref "D201") (pin "1") (pinfunction "C_1") (pintype "passive"))
      (node (ref "U202") (pin "7") (pinfunction "VB_7") (pintype "passive"))
    )
    (net (code "34") (name "Net-(D202-C)") (class "Default")
      (node (ref "C206") (pin "2") (pinfunction "2_2") (pintype "passive"))
      (node (ref "D202") (pin "1") (pinfunction "C_1") (pintype "passive"))
      (node (ref "U203") (pin "7") (pinfunction "VB_7") (pintype "passive"))
    )
    (net (code "35") (name "Net-(J200-Pad6)") (class "Default")
      (node (ref "J200") (pin "6") (pinfunction "6_6") (pintype "passive"))
      (node (ref "S201") (pin "3") (pinfunction "3_3") (pintype "passive"))
    )
    (net (code "36") (name "Net-(Q200-B)") (class "Default")
      (node (ref "Q200") (pin "1") (pinfunction "B_1") (pintype "passive"))
      (node (ref "R207") (pin "1") (pinfunction "1_1") (pintype "passive"))
    )
    (net (code "37") (name "Net-(Q201-B)") (class "Default")
      (node (ref "Q201") (pin "2") (pinfunction "B_2") (pintype "passive"))
      (node (ref "R215") (pin "2") (pinfunction "2_2") (pintype "passive"))
    )
    (net (code "38") (name "Net-(Q202-B)") (class "Default")
      (node (ref "Q202") (pin "2") (pinfunction "B_2") (pintype "passive"))
      (node (ref "R217") (pin "2") (pinfunction "2_2") (pintype "passive"))
    )
    (net (code "39") (name "Net-(Q203-B)") (class "Default")
      (node (ref "Q203") (pin "2") (pinfunction "B_2") (pintype "passive"))
      (node (ref "R220") (pin "2") (pinfunction "2_2") (pintype "passive"))
    )
    (net (code "40") (name "Net-(Q204-B)") (class "Default")
      (node (ref "Q204") (pin "2") (pinfunction "B_2") (pintype "passive"))
      (node (ref "R222") (pin "2") (pinfunction "2_2") (pintype "passive"))
    )
    (net (code "41") (name "Net-(U200-1IN+)") (class "Default")
      (node (ref "C215") (pin "2") (pinfunction "2_2") (pintype "passive"))
      (node (ref "J206") (pin "1") (pinfunction "1_1") (pintype "passive"))
      (node (ref "R200") (pin "1") (pinfunction "1_1") (pintype "passive"))
      (node (ref "R201") (pin "2") (pinfunction "2_2") (pintype "passive"))
      (node (ref "R203") (pin "1") (pinfunction "1_1") (pintype "passive"))
      (node (ref "U200") (pin "3") (pinfunction "1IN+_3") (pintype "passive"))
      (node (ref "U200") (pin "6") (pinfunction "2IN-_6") (pintype "passive"))
    )
    (net (code "42") (name "Net-(U200-1IN-)") (class "Default")
      (node (ref "C204") (pin "2") (pinfunction "2_2") (pintype "passive"))
      (node (ref "J204") (pin "1") (pinfunction "1_1") (pintype "passive"))
      (node (ref "R206") (pin "1") (pinfunction "1_1") (pintype "passive"))
      (node (ref "R209") (pin "2") (pinfunction "2_2") (pintype "passive"))
      (node (ref "U200") (pin "2") (pinfunction "1IN-_2") (pintype "passive"))
      (node (ref "U200") (pin "5") (pinfunction "2IN+_5") (pintype "passive"))
    )
    (net (code "43") (name "Net-(U200-2OUT)") (class "Default")
      (node (ref "C202") (pin "2") (pinfunction "2_2") (pintype "passive"))
      (node (ref "J203") (pin "1") (pinfunction "1_1") (pintype "passive"))
      (node (ref "R202") (pin "1") (pinfunction "1_1") (pintype "passive"))
      (node (ref "R205") (pin "2") (pinfunction "2_2") (pintype "passive"))
      (node (ref "U200") (pin "7") (pinfunction "2OUT_7") (pintype "passive"))
    )
    (net (code "44") (name "Net-(U201A-DT0)") (class "Default")
      (node (ref "S203") (pin "2") (pinfunction "2_2") (pintype "passive"))
      (node (ref "U201") (pin "2") (pinfunction "DT0_2") (pintype "input"))
    )
    (net (code "45") (name "Net-(U201A-DT1)") (class "Default")
      (node (ref "S202") (pin "2") (pinfunction "2_2") (pintype "passive"))
      (node (ref "U201") (pin "1") (pinfunction "DT1_1") (pintype "input"))
    )
    (net (code "46") (name "Net-(U201A-FREQSEL0)") (class "Default")
      (node (ref "S204") (pin "2") (pinfunction "2_2") (pintype "passive"))
      (node (ref "U201") (pin "18") (pinfunction "FREQSEL0_18") (pintype "input"))
    )
    (net (code "47") (name "Net-(U201A-LEDOUT)") (class "Default")
      (node (ref "D200") (pin "C") (pinfunction "C_C") (pintype "passive"))
      (node (ref "U201") (pin "8") (pinfunction "LEDOUT_8") (pintype "output"))
    )
    (net (code "48") (name "Net-(U201A-OSC1)") (class "Default")
      (node (ref "C220") (pin "1") (pinfunction "1_1") (pintype "passive"))
      (node (ref "J210") (pin "1") (pinfunction "1_1") (pintype "passive"))
      (node (ref "U201") (pin "10") (pinfunction "OSC1_10") (pintype "input"))
      (node (ref "Y200") (pin "2") (pinfunction "2_2") (pintype "passive"))
    )
    (net (code "49") (name "Net-(U201A-OSC2)") (class "Default")
      (node (ref "C223") (pin "1") (pinfunction "1_1") (pintype "passive"))
      (node (ref "U201") (pin "11") (pinfunction "OSC2_11") (pintype "output"))
      (node (ref "Y200") (pin "1") (pinfunction "1_1") (pintype "passive"))
    )
    (net (code "50") (name "Net-(U201A-SST)") (class "Default")
      (node (ref "S205") (pin "2") (pinfunction "2_2") (pintype "passive"))
      (node (ref "U201") (pin "21") (pinfunction "SST_21") (pintype "input"))
    )
    (net (code "51") (name "unconnected-(J200-Pad8)") (class "Default")
      (node (ref "J200") (pin "8") (pinfunction "8_8") (pintype "passive+no_connect"))
    )
    (net (code "52") (name "unconnected-(S200-MNT_1-Pad4)") (class "Default")
      (node (ref "S200") (pin "4") (pinfunction "MNT_1_4") (pintype "passive+no_connect"))
    )
    (net (code "53") (name "unconnected-(S200-MNT_2-Pad5)") (class "Default")
      (node (ref "S200") (pin "5") (pinfunction "MNT_2_5") (pintype "passive+no_connect"))
    )
    (net (code "54") (name "unconnected-(S201-MH1-Pad4)") (class "Default")
      (node (ref "S201") (pin "4") (pinfunction "MH1_4") (pintype "passive"))
    )
    (net (code "55") (name "unconnected-(S201-MH2-Pad5)") (class "Default")
      (node (ref "S201") (pin "5") (pinfunction "MH2_5") (pintype "passive"))
    )
    (net (code "56") (name "unconnected-(S201-Pad1)") (class "Default")
      (node (ref "S201") (pin "1") (pinfunction "1_1") (pintype "passive"))
    )
    (net (code "57") (name "unconnected-(S202-MH1-Pad4)") (class "Default")
      (node (ref "S202") (pin "4") (pinfunction "MH1_4") (pintype "passive"))
    )
    (net (code "58") (name "unconnected-(S202-MH2-Pad5)") (class "Default")
      (node (ref "S202") (pin "5") (pinfunction "MH2_5") (pintype "passive"))
    )
    (net (code "59") (name "unconnected-(S203-MH1-Pad4)") (class "Default")
      (node (ref "S203") (pin "4") (pinfunction "MH1_4") (pintype "passive"))
    )
    (net (code "60") (name "unconnected-(S203-MH2-Pad5)") (class "Default")
      (node (ref "S203") (pin "5") (pinfunction "MH2_5") (pintype "passive"))
    )
    (net (code "61") (name "unconnected-(S204-MH1-Pad4)") (class "Default")
      (node (ref "S204") (pin "4") (pinfunction "MH1_4") (pintype "passive"))
    )
    (net (code "62") (name "unconnected-(S204-MH2-Pad5)") (class "Default")
      (node (ref "S204") (pin "5") (pinfunction "MH2_5") (pintype "passive"))
    )
    (net (code "63") (name "unconnected-(S205-MH1-Pad4)") (class "Default")
      (node (ref "S205") (pin "4") (pinfunction "MH1_4") (pintype "passive"))
    )
    (net (code "64") (name "unconnected-(S205-MH2-Pad5)") (class "Default")
      (node (ref "S205") (pin "5") (pinfunction "MH2_5") (pintype "passive"))
    )
    (net (code "65") (name "unconnected-(U201A-RXD-Pad4)") (class "Default")
      (node (ref "U201") (pin "4") (pinfunction "RXD_4") (pintype "input+no_connect"))
    )
    (net (code "66") (name "unconnected-(U201B-NC-Pad22)") (class "Default")
      (node (ref "U201") (pin "22") (pinfunction "NC_22") (pintype "passive+no_connect"))
    )
    (net (code "67") (name "unconnected-(U202-N.C._1-Pad4)") (class "Default")
      (node (ref "U202") (pin "4") (pinfunction "N.C._1_4") (pintype "passive+no_connect"))
    )
    (net (code "68") (name "unconnected-(U202-N.C._2-Pad5)") (class "Default")
      (node (ref "U202") (pin "5") (pinfunction "N.C._2_5") (pintype "passive+no_connect"))
    )
    (net (code "69") (name "unconnected-(U202-N.C._3-Pad9)") (class "Default")
      (node (ref "U202") (pin "9") (pinfunction "N.C._3_9") (pintype "passive+no_connect"))
    )
    (net (code "70") (name "unconnected-(U202-N.C._4-Pad10)") (class "Default")
      (node (ref "U202") (pin "10") (pinfunction "N.C._4_10") (pintype "passive+no_connect"))
    )
    (net (code "71") (name "unconnected-(U202-N.C._5-Pad16)") (class "Default")
      (node (ref "U202") (pin "16") (pinfunction "N.C._5_16") (pintype "passive+no_connect"))
    )
    (net (code "72") (name "unconnected-(U203-N.C._1-Pad4)") (class "Default")
      (node (ref "U203") (pin "4") (pinfunction "N.C._1_4") (pintype "passive+no_connect"))
    )
    (net (code "73") (name "unconnected-(U203-N.C._2-Pad5)") (class "Default")
      (node (ref "U203") (pin "5") (pinfunction "N.C._2_5") (pintype "passive+no_connect"))
    )
    (net (code "74") (name "unconnected-(U203-N.C._3-Pad9)") (class "Default")
      (node (ref "U203") (pin "9") (pinfunction "N.C._3_9") (pintype "passive+no_connect"))
    )
    (net (code "75") (name "unconnected-(U203-N.C._4-Pad10)") (class "Default")
      (node (ref "U203") (pin "10") (pinfunction "N.C._4_10") (pintype "passive+no_connect"))
    )
    (net (code "76") (name "unconnected-(U203-N.C._5-Pad16)") (class "Default")
      (node (ref "U203") (pin "16") (pinfunction "N.C._5_16") (pintype "passive+no_connect"))
    )
  )
)
